# wr703n-display.net
KiCad netlist of a schematic drawn in EAGLE
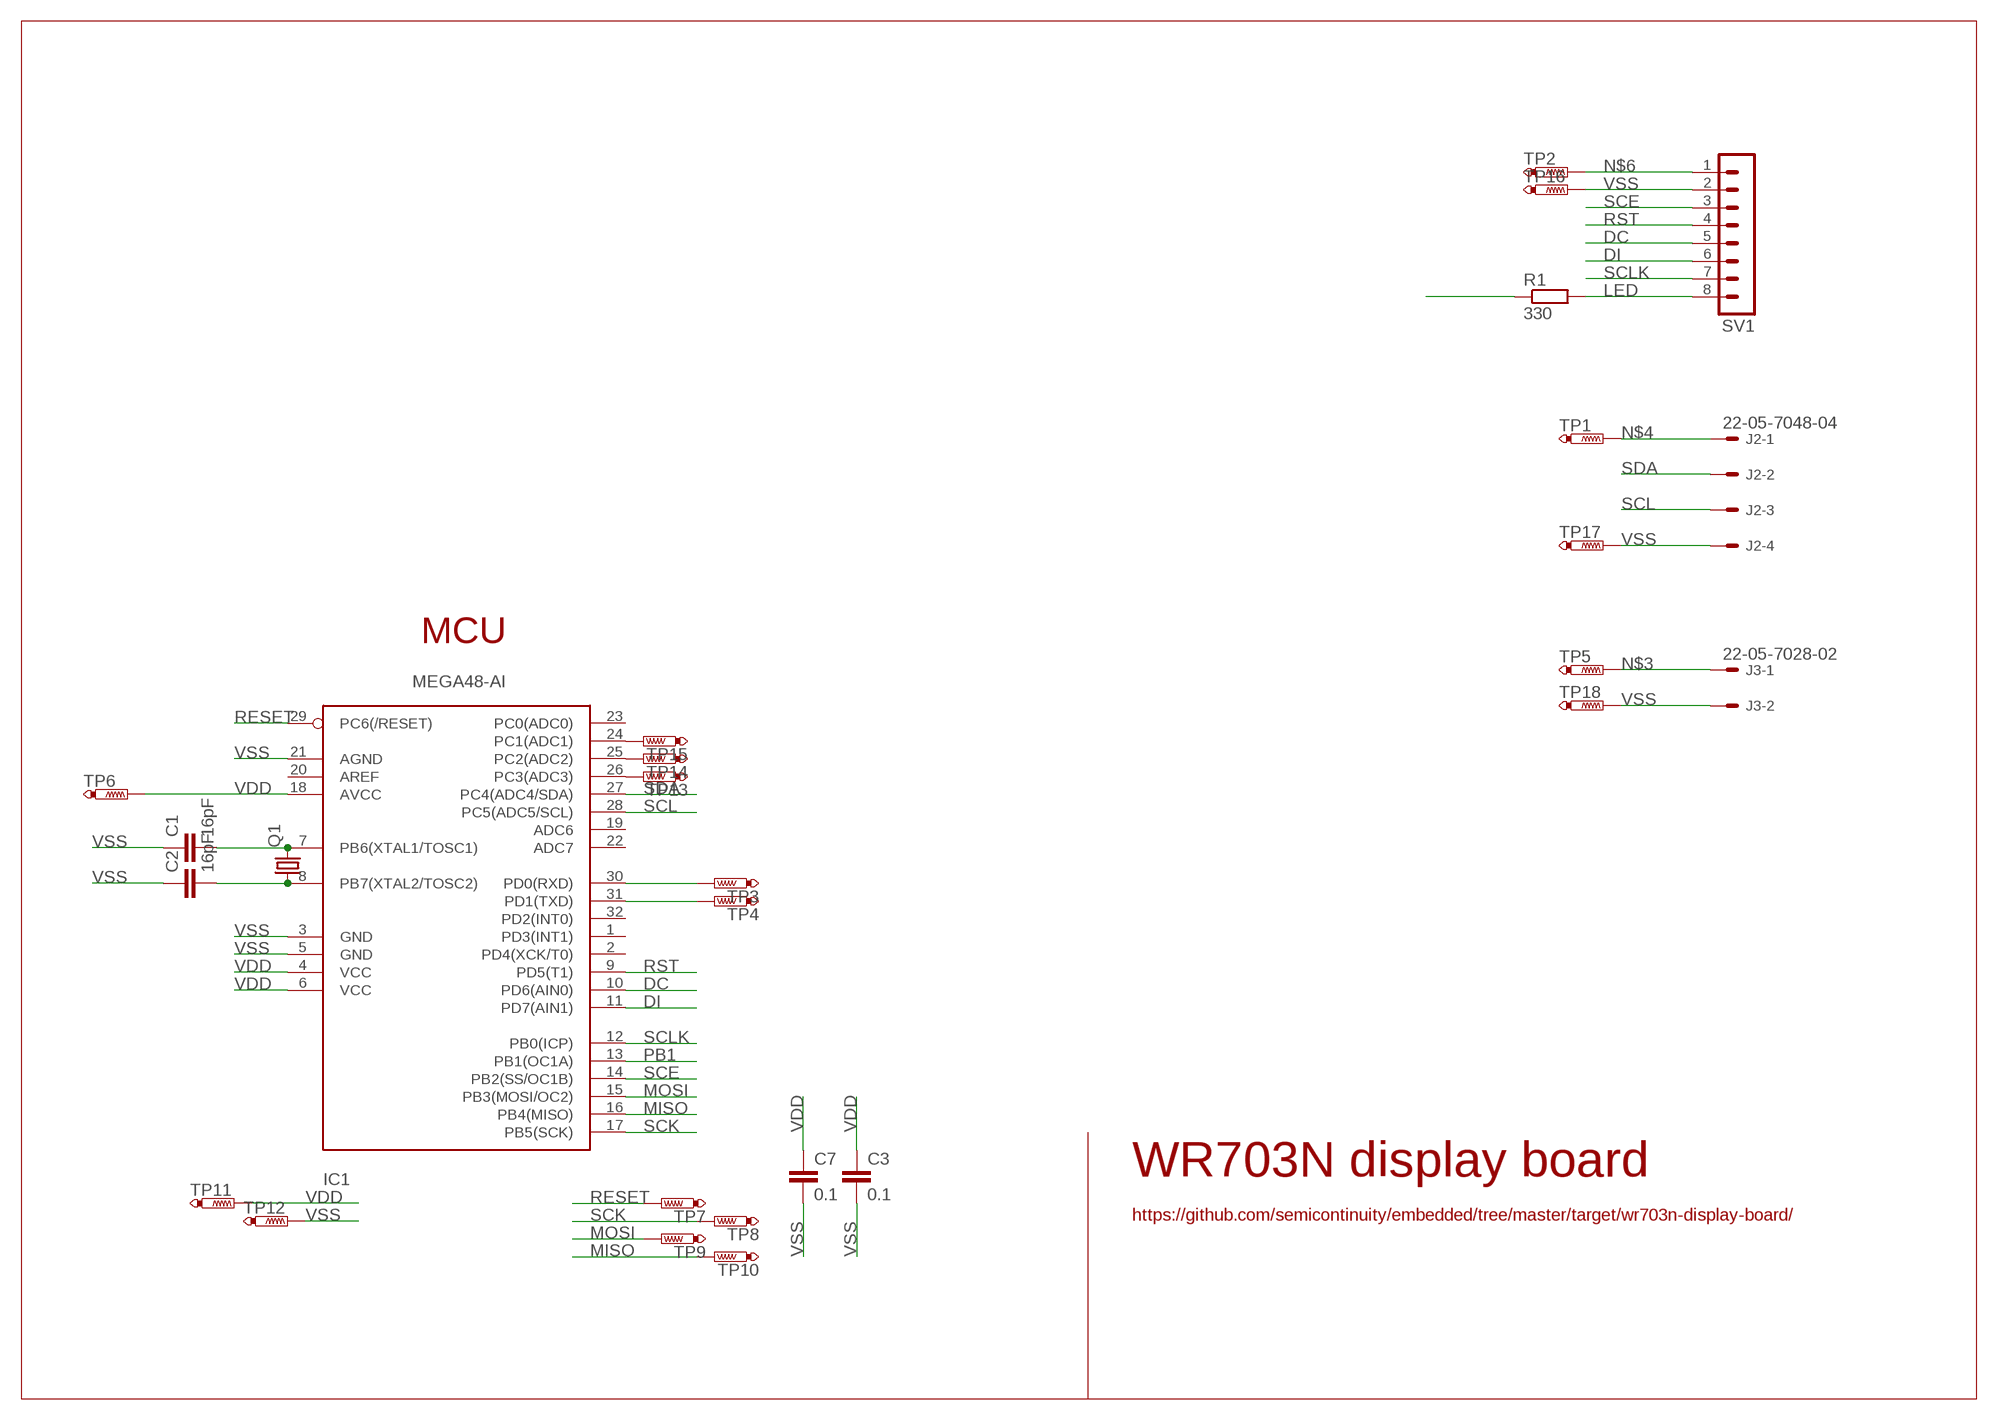
[diagram p0: schematic, sheet 1]

(export (version "E")
  (design (tool "Eeschema 10.0.6"))
  (components
    (comp (ref "C1")
      (value "16pF")
      (footprint "eagle-import:C0805")
      (libsource (lib "eagle-import") (part "C-EUC0805"))
    )
    (comp (ref "C2")
      (value "16pF")
      (footprint "eagle-import:C0805")
      (libsource (lib "eagle-import") (part "C-EUC0805"))
    )
    (comp (ref "C3")
      (value "0.1")
      (footprint "eagle-import:C0805")
      (libsource (lib "eagle-import") (part "C-EUC0805"))
    )
    (comp (ref "C7")
      (value "0.1")
      (footprint "eagle-import:C0805")
      (libsource (lib "eagle-import") (part "C-EUC0805"))
    )
    (comp (ref "IC1")
      (value "MEGA48-AI")
      (footprint "eagle-import:TQFP32-08")
      (libsource (lib "eagle-import") (part "MEGA8-AI"))
    )
    (comp (ref "J2")
      (value "22-05-7048-04")
      (footprint "eagle-import:7395-04")
      (libsource (lib "eagle-import") (part "22-?-0405-7048"))
    )
    (comp (ref "J3")
      (value "22-05-7028-02")
      (footprint "eagle-import:7395-02")
      (libsource (lib "eagle-import") (part "22-?-0205-7028"))
    )
    (comp (ref "Q1")
      (value "CRYSTALHC49S")
      (footprint "eagle-import:HC49_S")
      (libsource (lib "eagle-import") (part "CRYSTALHC49S"))
    )
    (comp (ref "R1")
      (value "330")
      (footprint "eagle-import:R0805")
      (libsource (lib "eagle-import") (part "R-EU_R0805"))
    )
    (comp (ref "SV1")
      (value "MA08-1")
      (footprint "eagle-import:MA08-1")
      (libsource (lib "eagle-import") (part "MA08-1"))
    )
    (comp (ref "TP1")
      (value "PTR1B2,54")
      (footprint "eagle-import:B2,54")
      (libsource (lib "eagle-import") (part "PTR1B2,54"))
    )
    (comp (ref "TP2")
      (value "PTR1B2,54")
      (footprint "eagle-import:B2,54")
      (libsource (lib "eagle-import") (part "PTR1B2,54"))
    )
    (comp (ref "TP3")
      (value "PTR1B2,54")
      (footprint "eagle-import:B2,54")
      (libsource (lib "eagle-import") (part "PTR1B2,54"))
    )
    (comp (ref "TP4")
      (value "PTR1B2,54")
      (footprint "eagle-import:B2,54")
      (libsource (lib "eagle-import") (part "PTR1B2,54"))
    )
    (comp (ref "TP5")
      (value "PTR1B2,54")
      (footprint "eagle-import:B2,54")
      (libsource (lib "eagle-import") (part "PTR1B2,54"))
    )
    (comp (ref "TP6")
      (value "PTR1B2,54")
      (footprint "eagle-import:B2,54")
      (libsource (lib "eagle-import") (part "PTR1B2,54"))
    )
    (comp (ref "TP7")
      (value "PTR1TP17R")
      (footprint "eagle-import:TP17R")
      (libsource (lib "eagle-import") (part "PTR1TP17R"))
    )
    (comp (ref "TP8")
      (value "PTR1TP17R")
      (footprint "eagle-import:TP17R")
      (libsource (lib "eagle-import") (part "PTR1TP17R"))
    )
    (comp (ref "TP9")
      (value "PTR1TP17R")
      (footprint "eagle-import:TP17R")
      (libsource (lib "eagle-import") (part "PTR1TP17R"))
    )
    (comp (ref "TP10")
      (value "PTR1TP17R")
      (footprint "eagle-import:TP17R")
      (libsource (lib "eagle-import") (part "PTR1TP17R"))
    )
    (comp (ref "TP11")
      (value "PTR1TP17R")
      (footprint "eagle-import:TP17R")
      (libsource (lib "eagle-import") (part "PTR1TP17R"))
    )
    (comp (ref "TP12")
      (value "PTR1TP17R")
      (footprint "eagle-import:TP17R")
      (libsource (lib "eagle-import") (part "PTR1TP17R"))
    )
    (comp (ref "TP13")
      (value "PTR1TP17R")
      (footprint "eagle-import:TP17R")
      (libsource (lib "eagle-import") (part "PTR1TP17R"))
    )
    (comp (ref "TP14")
      (value "PTR1TP17R")
      (footprint "eagle-import:TP17R")
      (libsource (lib "eagle-import") (part "PTR1TP17R"))
    )
    (comp (ref "TP15")
      (value "PTR1TP17R")
      (footprint "eagle-import:TP17R")
      (libsource (lib "eagle-import") (part "PTR1TP17R"))
    )
    (comp (ref "TP16")
      (value "PTR1B2,54")
      (footprint "eagle-import:B2,54")
      (libsource (lib "eagle-import") (part "PTR1B2,54"))
    )
    (comp (ref "TP17")
      (value "PTR1B2,54")
      (footprint "eagle-import:B2,54")
      (libsource (lib "eagle-import") (part "PTR1B2,54"))
    )
    (comp (ref "TP18")
      (value "PTR1B2,54")
      (footprint "eagle-import:B2,54")
      (libsource (lib "eagle-import") (part "PTR1B2,54"))
    )
  )
  (nets
    (net (code "1") (name "/DC") (class "Default")
      (node (ref "IC1") (pin "10") (pinfunction "PD6(AIN0)_10") (pintype "bidirectional"))
      (node (ref "SV1") (pin "5") (pinfunction "5_5") (pintype "passive"))
    )
    (net (code "2") (name "/DI") (class "Default")
      (node (ref "IC1") (pin "11") (pinfunction "PD7(AIN1)_11") (pintype "bidirectional"))
      (node (ref "SV1") (pin "6") (pinfunction "6_6") (pintype "passive"))
    )
    (net (code "3") (name "/LED") (class "Default")
      (node (ref "R1") (pin "2") (pinfunction "2_2") (pintype "passive"))
      (node (ref "SV1") (pin "8") (pinfunction "8_8") (pintype "passive"))
    )
    (net (code "4") (name "/MISO") (class "Default")
      (node (ref "IC1") (pin "16") (pinfunction "PB4(MISO)_16") (pintype "bidirectional"))
      (node (ref "TP10") (pin "TP") (pinfunction "TP_TP") (pintype "input"))
    )
    (net (code "5") (name "/MOSI") (class "Default")
      (node (ref "IC1") (pin "15") (pinfunction "PB3(MOSI/OC2)_15") (pintype "bidirectional"))
      (node (ref "TP9") (pin "TP") (pinfunction "TP_TP") (pintype "input"))
    )
    (net (code "6") (name "/N$3") (class "Default")
      (node (ref "J3") (pin "1") (pinfunction "S_1") (pintype "passive"))
      (node (ref "TP5") (pin "TP") (pinfunction "TP_TP") (pintype "input"))
    )
    (net (code "7") (name "/N$4") (class "Default")
      (node (ref "J2") (pin "1") (pinfunction "S_1") (pintype "passive"))
      (node (ref "TP1") (pin "TP") (pinfunction "TP_TP") (pintype "input"))
    )
    (net (code "8") (name "/N$6") (class "Default")
      (node (ref "SV1") (pin "1") (pinfunction "1_1") (pintype "passive"))
      (node (ref "TP2") (pin "TP") (pinfunction "TP_TP") (pintype "input"))
    )
    (net (code "9") (name "/PB1") (class "Default")
      (node (ref "IC1") (pin "13") (pinfunction "PB1(OC1A)_13") (pintype "bidirectional"))
      (node (ref "R1") (pin "1") (pinfunction "1_1") (pintype "passive"))
    )
    (net (code "10") (name "/RESET") (class "Default")
      (node (ref "IC1") (pin "29") (pinfunction "PC6(/RESET)_29") (pintype "bidirectional"))
      (node (ref "TP7") (pin "TP") (pinfunction "TP_TP") (pintype "input"))
    )
    (net (code "11") (name "/RST") (class "Default")
      (node (ref "IC1") (pin "9") (pinfunction "PD5(T1)_9") (pintype "bidirectional"))
      (node (ref "SV1") (pin "4") (pinfunction "4_4") (pintype "passive"))
    )
    (net (code "12") (name "/SCE") (class "Default")
      (node (ref "IC1") (pin "14") (pinfunction "PB2(SS/OC1B)_14") (pintype "bidirectional"))
      (node (ref "SV1") (pin "3") (pinfunction "3_3") (pintype "passive"))
    )
    (net (code "13") (name "/SCK") (class "Default")
      (node (ref "IC1") (pin "17") (pinfunction "PB5(SCK)_17") (pintype "bidirectional"))
      (node (ref "TP8") (pin "TP") (pinfunction "TP_TP") (pintype "input"))
    )
    (net (code "14") (name "/SCL") (class "Default")
      (node (ref "IC1") (pin "28") (pinfunction "PC5(ADC5/SCL)_28") (pintype "bidirectional"))
      (node (ref "J2") (pin "3") (pinfunction "S_3") (pintype "passive"))
    )
    (net (code "15") (name "/SCLK") (class "Default")
      (node (ref "IC1") (pin "12") (pinfunction "PB0(ICP)_12") (pintype "bidirectional"))
      (node (ref "SV1") (pin "7") (pinfunction "7_7") (pintype "passive"))
    )
    (net (code "16") (name "/SDA") (class "Default")
      (node (ref "IC1") (pin "27") (pinfunction "PC4(ADC4/SDA)_27") (pintype "bidirectional"))
      (node (ref "J2") (pin "2") (pinfunction "S_2") (pintype "passive"))
    )
    (net (code "17") (name "/VDD") (class "Default")
      (node (ref "C3") (pin "1") (pinfunction "1_1") (pintype "passive"))
      (node (ref "C7") (pin "1") (pinfunction "1_1") (pintype "passive"))
      (node (ref "IC1") (pin "18") (pinfunction "AVCC_18") (pintype "bidirectional"))
      (node (ref "IC1") (pin "4") (pinfunction "VCC_4") (pintype "bidirectional"))
      (node (ref "IC1") (pin "6") (pinfunction "VCC_6") (pintype "bidirectional"))
      (node (ref "TP11") (pin "TP") (pinfunction "TP_TP") (pintype "input"))
      (node (ref "TP6") (pin "TP") (pinfunction "TP_TP") (pintype "input"))
    )
    (net (code "18") (name "/VSS") (class "Default")
      (node (ref "C1") (pin "1") (pinfunction "1_1") (pintype "passive"))
      (node (ref "C2") (pin "1") (pinfunction "1_1") (pintype "passive"))
      (node (ref "C3") (pin "2") (pinfunction "2_2") (pintype "passive"))
      (node (ref "C7") (pin "2") (pinfunction "2_2") (pintype "passive"))
      (node (ref "IC1") (pin "21") (pinfunction "AGND_21") (pintype "bidirectional"))
      (node (ref "IC1") (pin "3") (pinfunction "GND_3") (pintype "bidirectional"))
      (node (ref "IC1") (pin "5") (pinfunction "GND_5") (pintype "bidirectional"))
      (node (ref "J2") (pin "4") (pinfunction "S_4") (pintype "passive"))
      (node (ref "J3") (pin "2") (pinfunction "S_2") (pintype "passive"))
      (node (ref "SV1") (pin "2") (pinfunction "2_2") (pintype "passive"))
      (node (ref "TP12") (pin "TP") (pinfunction "TP_TP") (pintype "input"))
      (node (ref "TP16") (pin "TP") (pinfunction "TP_TP") (pintype "input"))
      (node (ref "TP17") (pin "TP") (pinfunction "TP_TP") (pintype "input"))
      (node (ref "TP18") (pin "TP") (pinfunction "TP_TP") (pintype "input"))
    )
    (net (code "19") (name "Net-(IC1-PB6(XTAL1{slash}TOSC1))") (class "Default")
      (node (ref "C1") (pin "2") (pinfunction "2_2") (pintype "passive"))
      (node (ref "IC1") (pin "7") (pinfunction "PB6(XTAL1/TOSC1)_7") (pintype "bidirectional"))
      (node (ref "Q1") (pin "2") (pinfunction "2_2") (pintype "passive"))
    )
    (net (code "20") (name "Net-(IC1-PB7(XTAL2{slash}TOSC2))") (class "Default")
      (node (ref "C2") (pin "2") (pinfunction "2_2") (pintype "passive"))
      (node (ref "IC1") (pin "8") (pinfunction "PB7(XTAL2/TOSC2)_8") (pintype "bidirectional"))
      (node (ref "Q1") (pin "1") (pinfunction "1_1") (pintype "passive"))
    )
    (net (code "21") (name "Net-(IC1-PC1(ADC1))") (class "Default")
      (node (ref "IC1") (pin "24") (pinfunction "PC1(ADC1)_24") (pintype "bidirectional"))
      (node (ref "TP15") (pin "TP") (pinfunction "TP_TP") (pintype "input"))
    )
    (net (code "22") (name "Net-(IC1-PC2(ADC2))") (class "Default")
      (node (ref "IC1") (pin "25") (pinfunction "PC2(ADC2)_25") (pintype "bidirectional"))
      (node (ref "TP14") (pin "TP") (pinfunction "TP_TP") (pintype "input"))
    )
    (net (code "23") (name "Net-(IC1-PC3(ADC3))") (class "Default")
      (node (ref "IC1") (pin "26") (pinfunction "PC3(ADC3)_26") (pintype "bidirectional"))
      (node (ref "TP13") (pin "TP") (pinfunction "TP_TP") (pintype "input"))
    )
    (net (code "24") (name "Net-(IC1-PD0(RXD))") (class "Default")
      (node (ref "IC1") (pin "30") (pinfunction "PD0(RXD)_30") (pintype "bidirectional"))
      (node (ref "TP3") (pin "TP") (pinfunction "TP_TP") (pintype "input"))
    )
    (net (code "25") (name "Net-(IC1-PD1(TXD))") (class "Default")
      (node (ref "IC1") (pin "31") (pinfunction "PD1(TXD)_31") (pintype "bidirectional"))
      (node (ref "TP4") (pin "TP") (pinfunction "TP_TP") (pintype "input"))
    )
    (net (code "26") (name "unconnected-(IC1-ADC6-Pad19)") (class "Default")
      (node (ref "IC1") (pin "19") (pinfunction "ADC6_19") (pintype "bidirectional"))
    )
    (net (code "27") (name "unconnected-(IC1-ADC7-Pad22)") (class "Default")
      (node (ref "IC1") (pin "22") (pinfunction "ADC7_22") (pintype "bidirectional"))
    )
    (net (code "28") (name "unconnected-(IC1-AREF-Pad20)") (class "Default")
      (node (ref "IC1") (pin "20") (pinfunction "AREF_20") (pintype "bidirectional"))
    )
    (net (code "29") (name "unconnected-(IC1-PC0(ADC0)-Pad23)") (class "Default")
      (node (ref "IC1") (pin "23") (pinfunction "PC0(ADC0)_23") (pintype "bidirectional"))
    )
    (net (code "30") (name "unconnected-(IC1-PD2(INT0)-Pad32)") (class "Default")
      (node (ref "IC1") (pin "32") (pinfunction "PD2(INT0)_32") (pintype "bidirectional"))
    )
    (net (code "31") (name "unconnected-(IC1-PD3(INT1)-Pad1)") (class "Default")
      (node (ref "IC1") (pin "1") (pinfunction "PD3(INT1)_1") (pintype "bidirectional"))
    )
    (net (code "32") (name "unconnected-(IC1-PD4(XCK{slash}T0)-Pad2)") (class "Default")
      (node (ref "IC1") (pin "2") (pinfunction "PD4(XCK/T0)_2") (pintype "bidirectional"))
    )
  )
)
